# SlopeGenerator.net
KiCad netlist of a schematic drawn in EAGLE
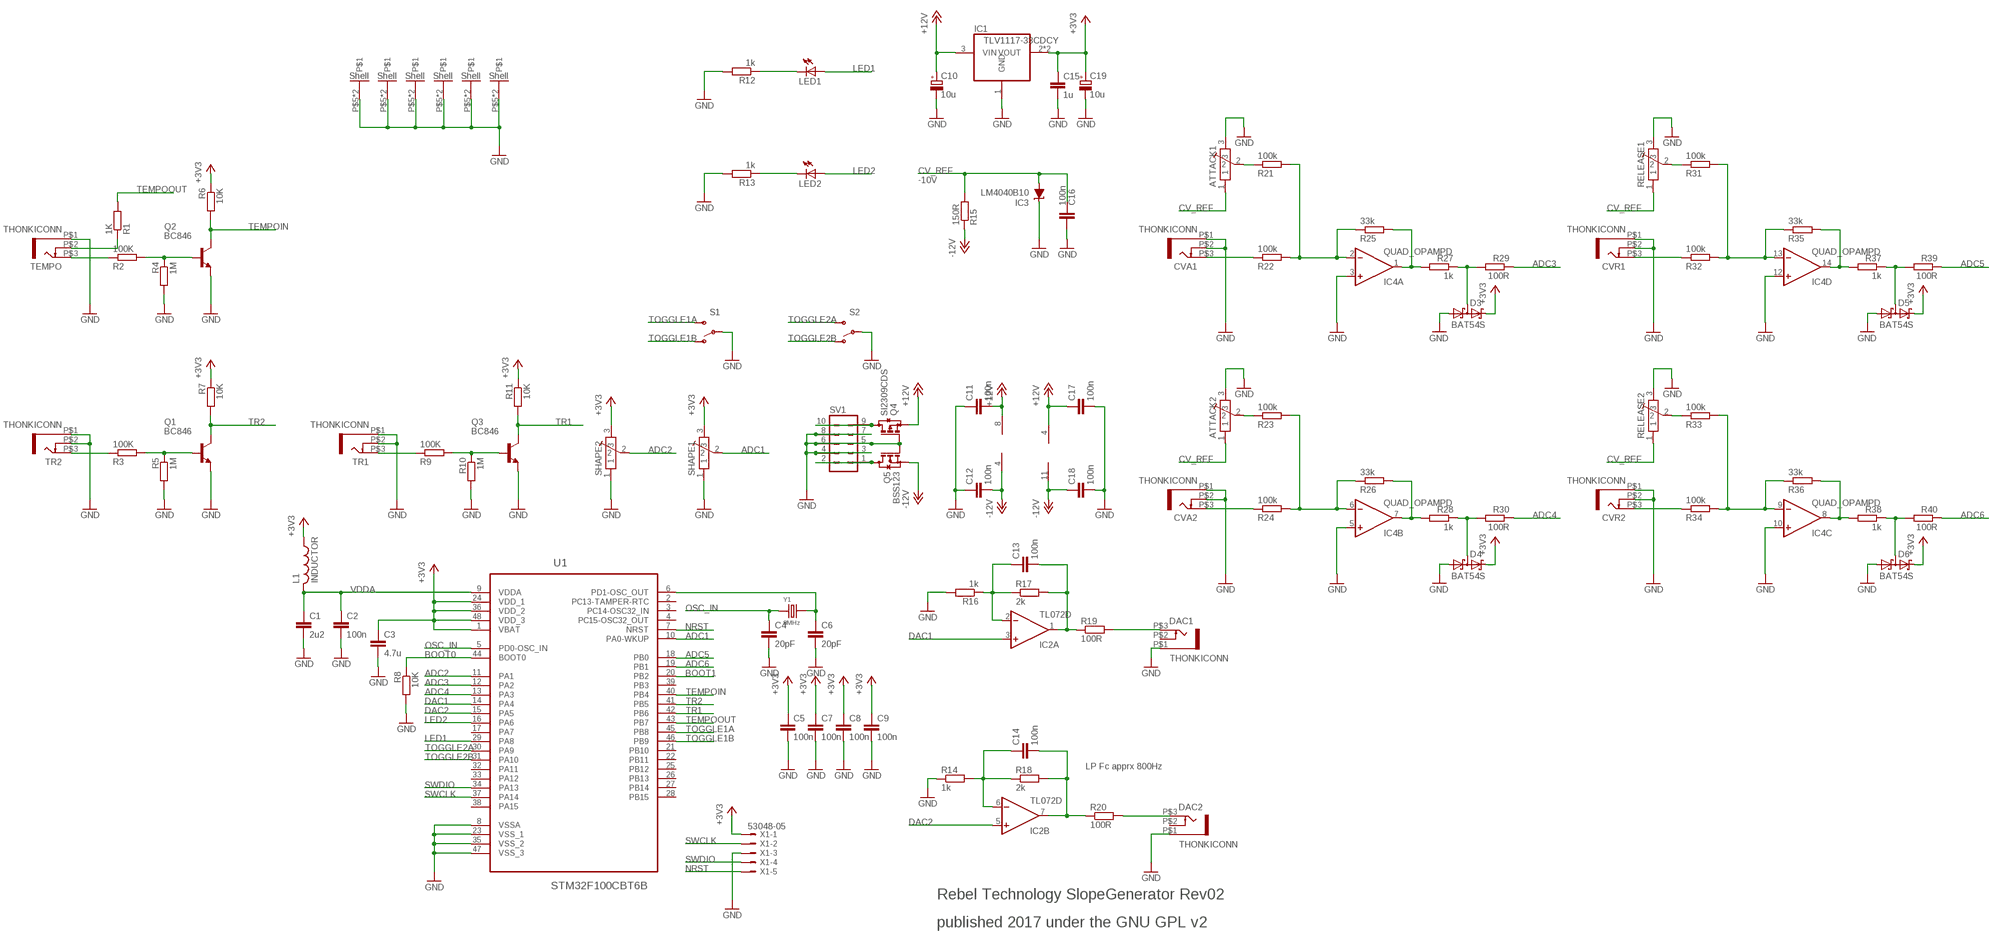
[diagram p0: schematic, sheet 1]

(export (version "E")
  (design (tool "Eeschema 10.0.6"))
  (components
    (comp (ref "ATTACK1")
      (value "POT-ALPS-RK09L1140")
      (footprint "eagle-import:POT-ALPS-RK09L1140")
      (libsource (lib "eagle-import") (part "POT-ALPS-RK09L1140"))
    )
    (comp (ref "ATTACK2")
      (value "POT-ALPS-RK09L1140")
      (footprint "eagle-import:POT-ALPS-RK09L1140")
      (libsource (lib "eagle-import") (part "POT-ALPS-RK09L1140"))
    )
    (comp (ref "C1")
      (value "2u2")
      (footprint "eagle-import:C0603")
      (libsource (lib "eagle-import") (part "C-EUC0603"))
    )
    (comp (ref "C2")
      (value "100n")
      (footprint "eagle-import:C0603")
      (libsource (lib "eagle-import") (part "C-EUC0603"))
    )
    (comp (ref "C3")
      (value "4.7u")
      (footprint "eagle-import:C0603")
      (libsource (lib "eagle-import") (part "C-EUC0603"))
    )
    (comp (ref "C4")
      (value "20pF")
      (footprint "eagle-import:C0603")
      (libsource (lib "eagle-import") (part "C-EUC0603"))
    )
    (comp (ref "C5")
      (value "100n")
      (footprint "eagle-import:C0603")
      (libsource (lib "eagle-import") (part "C-EUC0603"))
    )
    (comp (ref "C6")
      (value "20pF")
      (footprint "eagle-import:C0603")
      (libsource (lib "eagle-import") (part "C-EUC0603"))
    )
    (comp (ref "C7")
      (value "100n")
      (footprint "eagle-import:C0603")
      (libsource (lib "eagle-import") (part "C-EUC0603"))
    )
    (comp (ref "C8")
      (value "100n")
      (footprint "eagle-import:C0603")
      (libsource (lib "eagle-import") (part "C-EUC0603"))
    )
    (comp (ref "C9")
      (value "100n")
      (footprint "eagle-import:C0603")
      (libsource (lib "eagle-import") (part "C-EUC0603"))
    )
    (comp (ref "C10")
      (value "10u")
      (footprint "eagle-import:153CLV-0405")
      (libsource (lib "eagle-import") (part "CPOL-EU153CLV-0405"))
    )
    (comp (ref "C11")
      (value "100n")
      (footprint "eagle-import:C0603")
      (libsource (lib "eagle-import") (part "C-EUC0603"))
    )
    (comp (ref "C12")
      (value "100n")
      (footprint "eagle-import:C0603")
      (libsource (lib "eagle-import") (part "C-EUC0603"))
    )
    (comp (ref "C13")
      (value "100n")
      (footprint "eagle-import:C0603")
      (libsource (lib "eagle-import") (part "C-EUC0603"))
    )
    (comp (ref "C14")
      (value "100n")
      (footprint "eagle-import:C0603")
      (libsource (lib "eagle-import") (part "C-EUC0603"))
    )
    (comp (ref "C15")
      (value "1u")
      (footprint "eagle-import:C0603")
      (libsource (lib "eagle-import") (part "C-EUC0603"))
    )
    (comp (ref "C16")
      (value "100n")
      (footprint "eagle-import:C0603")
      (libsource (lib "eagle-import") (part "C-EUC0603"))
    )
    (comp (ref "C17")
      (value "100n")
      (footprint "eagle-import:C0603")
      (libsource (lib "eagle-import") (part "C-EUC0603"))
    )
    (comp (ref "C18")
      (value "100n")
      (footprint "eagle-import:C0603")
      (libsource (lib "eagle-import") (part "C-EUC0603"))
    )
    (comp (ref "C19")
      (value "10u")
      (footprint "eagle-import:153CLV-0405")
      (libsource (lib "eagle-import") (part "CPOL-EU153CLV-0405"))
    )
    (comp (ref "CVA1")
      (value "THONKICONN")
      (footprint "eagle-import:THONKICONN")
      (libsource (lib "eagle-import") (part "THONKICONN"))
    )
    (comp (ref "CVA2")
      (value "THONKICONN")
      (footprint "eagle-import:THONKICONN")
      (libsource (lib "eagle-import") (part "THONKICONN"))
    )
    (comp (ref "CVR1")
      (value "THONKICONN")
      (footprint "eagle-import:THONKICONN")
      (libsource (lib "eagle-import") (part "THONKICONN"))
    )
    (comp (ref "CVR2")
      (value "THONKICONN")
      (footprint "eagle-import:THONKICONN")
      (libsource (lib "eagle-import") (part "THONKICONN"))
    )
    (comp (ref "D3")
      (value "BAT54S")
      (footprint "eagle-import:SOT23")
      (libsource (lib "eagle-import") (part "BAT54S"))
    )
    (comp (ref "D4")
      (value "BAT54S")
      (footprint "eagle-import:SOT23")
      (libsource (lib "eagle-import") (part "BAT54S"))
    )
    (comp (ref "D5")
      (value "BAT54S")
      (footprint "eagle-import:SOT23")
      (libsource (lib "eagle-import") (part "BAT54S"))
    )
    (comp (ref "D6")
      (value "BAT54S")
      (footprint "eagle-import:SOT23")
      (libsource (lib "eagle-import") (part "BAT54S"))
    )
    (comp (ref "DAC1")
      (value "THONKICONN")
      (footprint "eagle-import:THONKICONN")
      (libsource (lib "eagle-import") (part "THONKICONN"))
    )
    (comp (ref "DAC2")
      (value "THONKICONN")
      (footprint "eagle-import:THONKICONN")
      (libsource (lib "eagle-import") (part "THONKICONN"))
    )
    (comp (ref "IC1")
      (value "TLV1117-33CDCY")
      (footprint "eagle-import:SOT223")
      (fields (field (name "MPN") "REG1117"))
      (libsource (lib "eagle-import") (part "REG1117"))
    )
    (comp (ref "IC2")
      (value "TL072D")
      (footprint "eagle-import:SO08")
      (libsource (lib "eagle-import") (part "TL072D"))
    )
    (comp (ref "IC3")
      (value "LM4040B10")
      (footprint "eagle-import:DBZ_R-PDSO-G3")
      (fields (field (name "MF") "TEXAS INSTRUMENT CONNECTORS") (field (name "MPN") "LM4041C12QDBZT"))
      (libsource (lib "eagle-import") (part "LM4041DBZC12"))
    )
    (comp (ref "IC4")
      (value "QUAD_OPAMPD")
      (footprint "eagle-import:SO14")
      (libsource (lib "eagle-import") (part "QUAD_OPAMPD"))
    )
    (comp (ref "L1")
      (value "INDUCTOR")
      (footprint "eagle-import:0603")
      (libsource (lib "eagle-import") (part "INDUCTOR"))
    )
    (comp (ref "LED1")
      (value "LED3MM")
      (footprint "eagle-import:LED3MM")
      (libsource (lib "eagle-import") (part "LED3MM"))
    )
    (comp (ref "LED2")
      (value "LED3MM")
      (footprint "eagle-import:LED3MM")
      (libsource (lib "eagle-import") (part "LED3MM"))
    )
    (comp (ref "Q1")
      (value "BC846")
      (footprint "eagle-import:SOT23")
      (libsource (lib "eagle-import") (part "BC846"))
    )
    (comp (ref "Q2")
      (value "BC846")
      (footprint "eagle-import:SOT23")
      (libsource (lib "eagle-import") (part "BC846"))
    )
    (comp (ref "Q3")
      (value "BC846")
      (footprint "eagle-import:SOT23")
      (libsource (lib "eagle-import") (part "BC846"))
    )
    (comp (ref "Q4")
      (value "SI2309CDS")
      (footprint "eagle-import:SOT23")
      (libsource (lib "eagle-import") (part "BSS84"))
    )
    (comp (ref "Q5")
      (value "BSS123")
      (footprint "eagle-import:SOT23")
      (libsource (lib "eagle-import") (part "BSS123"))
    )
    (comp (ref "R1")
      (value "1K")
      (footprint "eagle-import:0603")
      (libsource (lib "eagle-import") (part "R-EU_0603"))
    )
    (comp (ref "R2")
      (value "100K")
      (footprint "eagle-import:0603")
      (libsource (lib "eagle-import") (part "R-EU_0603"))
    )
    (comp (ref "R3")
      (value "100K")
      (footprint "eagle-import:0603")
      (libsource (lib "eagle-import") (part "R-EU_0603"))
    )
    (comp (ref "R4")
      (value "1M")
      (footprint "eagle-import:0603")
      (libsource (lib "eagle-import") (part "R-EU_0603"))
    )
    (comp (ref "R5")
      (value "1M")
      (footprint "eagle-import:0603")
      (libsource (lib "eagle-import") (part "R-EU_0603"))
    )
    (comp (ref "R6")
      (value "10K")
      (footprint "eagle-import:0603")
      (libsource (lib "eagle-import") (part "R-EU_0603"))
    )
    (comp (ref "R7")
      (value "10K")
      (footprint "eagle-import:0603")
      (libsource (lib "eagle-import") (part "R-EU_0603"))
    )
    (comp (ref "R8")
      (value "10K")
      (footprint "eagle-import:0603")
      (libsource (lib "eagle-import") (part "R-EU_0603"))
    )
    (comp (ref "R9")
      (value "100K")
      (footprint "eagle-import:0603")
      (libsource (lib "eagle-import") (part "R-EU_0603"))
    )
    (comp (ref "R10")
      (value "1M")
      (footprint "eagle-import:0603")
      (libsource (lib "eagle-import") (part "R-EU_0603"))
    )
    (comp (ref "R11")
      (value "10K")
      (footprint "eagle-import:0603")
      (libsource (lib "eagle-import") (part "R-EU_0603"))
    )
    (comp (ref "R12")
      (value "1k")
      (footprint "eagle-import:0603")
      (libsource (lib "eagle-import") (part "R-EU_0603"))
    )
    (comp (ref "R13")
      (value "1k")
      (footprint "eagle-import:0603")
      (libsource (lib "eagle-import") (part "R-EU_0603"))
    )
    (comp (ref "R14")
      (value "1k")
      (footprint "eagle-import:0603")
      (libsource (lib "eagle-import") (part "R-EU_0603"))
    )
    (comp (ref "R15")
      (value "150R")
      (footprint "eagle-import:0603")
      (libsource (lib "eagle-import") (part "R-EU_0603"))
    )
    (comp (ref "R16")
      (value "1k")
      (footprint "eagle-import:0603")
      (libsource (lib "eagle-import") (part "R-EU_0603"))
    )
    (comp (ref "R17")
      (value "2k")
      (footprint "eagle-import:0603")
      (libsource (lib "eagle-import") (part "R-EU_0603"))
    )
    (comp (ref "R18")
      (value "2k")
      (footprint "eagle-import:0603")
      (libsource (lib "eagle-import") (part "R-EU_0603"))
    )
    (comp (ref "R19")
      (value "100R")
      (footprint "eagle-import:0603")
      (libsource (lib "eagle-import") (part "R-EU_0603"))
    )
    (comp (ref "R20")
      (value "100R")
      (footprint "eagle-import:0603")
      (libsource (lib "eagle-import") (part "R-EU_0603"))
    )
    (comp (ref "R21")
      (value "100k")
      (footprint "eagle-import:0603")
      (libsource (lib "eagle-import") (part "R-EU_0603"))
    )
    (comp (ref "R22")
      (value "100k")
      (footprint "eagle-import:0603")
      (libsource (lib "eagle-import") (part "R-EU_0603"))
    )
    (comp (ref "R23")
      (value "100k")
      (footprint "eagle-import:0603")
      (libsource (lib "eagle-import") (part "R-EU_0603"))
    )
    (comp (ref "R24")
      (value "100k")
      (footprint "eagle-import:0603")
      (libsource (lib "eagle-import") (part "R-EU_0603"))
    )
    (comp (ref "R25")
      (value "33k")
      (footprint "eagle-import:0603")
      (libsource (lib "eagle-import") (part "R-EU_0603"))
    )
    (comp (ref "R26")
      (value "33k")
      (footprint "eagle-import:0603")
      (libsource (lib "eagle-import") (part "R-EU_0603"))
    )
    (comp (ref "R27")
      (value "1k")
      (footprint "eagle-import:0603")
      (libsource (lib "eagle-import") (part "R-EU_0603"))
    )
    (comp (ref "R28")
      (value "1k")
      (footprint "eagle-import:0603")
      (libsource (lib "eagle-import") (part "R-EU_0603"))
    )
    (comp (ref "R29")
      (value "100R")
      (footprint "eagle-import:0603")
      (libsource (lib "eagle-import") (part "R-EU_0603"))
    )
    (comp (ref "R30")
      (value "100R")
      (footprint "eagle-import:0603")
      (libsource (lib "eagle-import") (part "R-EU_0603"))
    )
    (comp (ref "R31")
      (value "100k")
      (footprint "eagle-import:0603")
      (libsource (lib "eagle-import") (part "R-EU_0603"))
    )
    (comp (ref "R32")
      (value "100k")
      (footprint "eagle-import:0603")
      (libsource (lib "eagle-import") (part "R-EU_0603"))
    )
    (comp (ref "R33")
      (value "100k")
      (footprint "eagle-import:0603")
      (libsource (lib "eagle-import") (part "R-EU_0603"))
    )
    (comp (ref "R34")
      (value "100k")
      (footprint "eagle-import:0603")
      (libsource (lib "eagle-import") (part "R-EU_0603"))
    )
    (comp (ref "R35")
      (value "33k")
      (footprint "eagle-import:0603")
      (libsource (lib "eagle-import") (part "R-EU_0603"))
    )
    (comp (ref "R36")
      (value "33k")
      (footprint "eagle-import:0603")
      (libsource (lib "eagle-import") (part "R-EU_0603"))
    )
    (comp (ref "R37")
      (value "1k")
      (footprint "eagle-import:0603")
      (libsource (lib "eagle-import") (part "R-EU_0603"))
    )
    (comp (ref "R38")
      (value "1k")
      (footprint "eagle-import:0603")
      (libsource (lib "eagle-import") (part "R-EU_0603"))
    )
    (comp (ref "R39")
      (value "100R")
      (footprint "eagle-import:0603")
      (libsource (lib "eagle-import") (part "R-EU_0603"))
    )
    (comp (ref "R40")
      (value "100R")
      (footprint "eagle-import:0603")
      (libsource (lib "eagle-import") (part "R-EU_0603"))
    )
    (comp (ref "RELEASE1")
      (value "POT-ALPS-RK09L1140")
      (footprint "eagle-import:POT-ALPS-RK09L1140")
      (libsource (lib "eagle-import") (part "POT-ALPS-RK09L1140"))
    )
    (comp (ref "RELEASE2")
      (value "POT-ALPS-RK09L1140")
      (footprint "eagle-import:POT-ALPS-RK09L1140")
      (libsource (lib "eagle-import") (part "POT-ALPS-RK09L1140"))
    )
    (comp (ref "S1")
      (value "SWITCH-SPST")
      (footprint "eagle-import:SWITCH-SPDT-SALECOM-T8014")
      (libsource (lib "eagle-import") (part "SWITCH-SPST"))
    )
    (comp (ref "S2")
      (value "SWITCH-SPST")
      (footprint "eagle-import:SWITCH-SPDT-SALECOM-T8014")
      (libsource (lib "eagle-import") (part "SWITCH-SPST"))
    )
    (comp (ref "SHAPE1")
      (value "POT-ALPS-RK09L1140")
      (footprint "eagle-import:POT-ALPS-RK09L1140")
      (libsource (lib "eagle-import") (part "POT-ALPS-RK09L1140"))
    )
    (comp (ref "SHAPE2")
      (value "POT-ALPS-RK09L1140")
      (footprint "eagle-import:POT-ALPS-RK09L1140")
      (libsource (lib "eagle-import") (part "POT-ALPS-RK09L1140"))
    )
    (comp (ref "SV1")
      (value "MA05-2")
      (footprint "eagle-import:MA05-2")
      (libsource (lib "eagle-import") (part "MA05-2"))
    )
    (comp (ref "TEMPO")
      (value "THONKICONN")
      (footprint "eagle-import:THONKICONN")
      (libsource (lib "eagle-import") (part "THONKICONN"))
    )
    (comp (ref "TR1")
      (value "THONKICONN")
      (footprint "eagle-import:THONKICONN")
      (libsource (lib "eagle-import") (part "THONKICONN"))
    )
    (comp (ref "TR2")
      (value "THONKICONN")
      (footprint "eagle-import:THONKICONN")
      (libsource (lib "eagle-import") (part "THONKICONN"))
    )
    (comp (ref "U1")
      (value "STM32F100CBT6B")
      (footprint "eagle-import:QFP50P900X900X160-48N")
      (libsource (lib "eagle-import") (part "STM32F100CBT6B"))
    )
    (comp (ref "X1")
      (value "53048-05")
      (footprint "eagle-import:53048-05")
      (fields (field (name "MF") "MOLEX") (field (name "MPN") "53048-0510"))
      (libsource (lib "eagle-import") (part "53?-05048"))
    )
    (comp (ref "Y1")
      (value "8MHz")
      (footprint "eagle-import:X2-SMD-5.0X3.2X1.3MM")
      (fields (field (name "MPN") "5032/2P"))
      (libsource (lib "eagle-import") (part "SMD-CRYSTAL-8MHZ-20PF-20PPM(2P-5.0X3.2MM)"))
    )
  )
  (nets
    (net (code "1") (name "+3V3") (class "Default")
      (node (ref "C15") (pin "1") (pinfunction "1_1") (pintype "passive"))
      (node (ref "C19") (pin "+") (pinfunction "+_+") (pintype "passive"))
      (node (ref "C3") (pin "1") (pinfunction "1_1") (pintype "passive"))
      (node (ref "C5") (pin "1") (pinfunction "1_1") (pintype "passive"))
      (node (ref "C7") (pin "1") (pinfunction "1_1") (pintype "passive"))
      (node (ref "C8") (pin "1") (pinfunction "1_1") (pintype "passive"))
      (node (ref "C9") (pin "1") (pinfunction "1_1") (pintype "passive"))
      (node (ref "D3") (pin "2") (pinfunction "C2_2") (pintype "passive"))
      (node (ref "D4") (pin "2") (pinfunction "C2_2") (pintype "passive"))
      (node (ref "D5") (pin "2") (pinfunction "C2_2") (pintype "passive"))
      (node (ref "D6") (pin "2") (pinfunction "C2_2") (pintype "passive"))
      (node (ref "IC1") (pin "2") (pinfunction "VOUT_2") (pintype "output"))
      (node (ref "IC1") (pin "4") (pinfunction "VOUT_4") (pintype "output"))
      (node (ref "L1") (pin "1") (pinfunction "1_1") (pintype "passive"))
      (node (ref "R11") (pin "1") (pinfunction "1_1") (pintype "passive"))
      (node (ref "R6") (pin "1") (pinfunction "1_1") (pintype "passive"))
      (node (ref "R7") (pin "1") (pinfunction "1_1") (pintype "passive"))
      (node (ref "SHAPE1") (pin "3") (pinfunction "3_3") (pintype "bidirectional"))
      (node (ref "SHAPE2") (pin "3") (pinfunction "3_3") (pintype "bidirectional"))
      (node (ref "U1") (pin "1") (pinfunction "VBAT_1") (pintype "power_in"))
      (node (ref "U1") (pin "24") (pinfunction "VDD_1_24") (pintype "power_in"))
      (node (ref "U1") (pin "36") (pinfunction "VDD_2_36") (pintype "power_in"))
      (node (ref "U1") (pin "48") (pinfunction "VDD_3_48") (pintype "power_in"))
      (node (ref "X1") (pin "1") (pinfunction "S_1") (pintype "passive"))
    )
    (net (code "2") (name "+12V") (class "Default")
      (node (ref "C10") (pin "+") (pinfunction "+_+") (pintype "passive"))
      (node (ref "C11") (pin "2") (pinfunction "2_2") (pintype "passive"))
      (node (ref "C17") (pin "1") (pinfunction "1_1") (pintype "passive"))
      (node (ref "IC1") (pin "3") (pinfunction "VIN_3") (pintype "input"))
      (node (ref "IC2") (pin "8") (pinfunction "V+_8") (pintype "power_in"))
      (node (ref "IC4") (pin "4") (pinfunction "V+_4") (pintype "power_in"))
      (node (ref "Q4") (pin "2") (pinfunction "S_2") (pintype "passive"))
    )
    (net (code "3") (name "-12V") (class "Default")
      (node (ref "C12") (pin "2") (pinfunction "2_2") (pintype "passive"))
      (node (ref "C18") (pin "1") (pinfunction "1_1") (pintype "passive"))
      (node (ref "IC2") (pin "4") (pinfunction "V-_4") (pintype "power_in"))
      (node (ref "IC4") (pin "11") (pinfunction "V-_11") (pintype "power_in"))
      (node (ref "Q5") (pin "2") (pinfunction "S_2") (pintype "passive"))
      (node (ref "R15") (pin "1") (pinfunction "1_1") (pintype "passive"))
    )
    (net (code "4") (name "/ADC1") (class "Default")
      (node (ref "SHAPE1") (pin "2") (pinfunction "2_2") (pintype "bidirectional"))
      (node (ref "U1") (pin "10") (pinfunction "PA0-WKUP_10") (pintype "bidirectional"))
    )
    (net (code "5") (name "/ADC2") (class "Default")
      (node (ref "SHAPE2") (pin "2") (pinfunction "2_2") (pintype "bidirectional"))
      (node (ref "U1") (pin "11") (pinfunction "PA1_11") (pintype "bidirectional"))
    )
    (net (code "6") (name "/ADC3") (class "Default")
      (node (ref "R29") (pin "1") (pinfunction "1_1") (pintype "passive"))
      (node (ref "U1") (pin "12") (pinfunction "PA2_12") (pintype "bidirectional"))
    )
    (net (code "7") (name "/ADC4") (class "Default")
      (node (ref "R30") (pin "1") (pinfunction "1_1") (pintype "passive"))
      (node (ref "U1") (pin "13") (pinfunction "PA3_13") (pintype "bidirectional"))
    )
    (net (code "8") (name "/ADC5") (class "Default")
      (node (ref "R39") (pin "1") (pinfunction "1_1") (pintype "passive"))
      (node (ref "U1") (pin "18") (pinfunction "PB0_18") (pintype "bidirectional"))
    )
    (net (code "9") (name "/ADC6") (class "Default")
      (node (ref "R40") (pin "1") (pinfunction "1_1") (pintype "passive"))
      (node (ref "U1") (pin "19") (pinfunction "PB1_19") (pintype "bidirectional"))
    )
    (net (code "10") (name "/BOOT0") (class "Default")
      (node (ref "R8") (pin "1") (pinfunction "1_1") (pintype "passive"))
      (node (ref "U1") (pin "44") (pinfunction "BOOT0_44") (pintype "input"))
    )
    (net (code "11") (name "/BOOT1") (class "Default")
      (node (ref "U1") (pin "20") (pinfunction "PB2_20") (pintype "bidirectional"))
    )
    (net (code "12") (name "/CV_REF") (class "Default")
      (node (ref "ATTACK1") (pin "1") (pinfunction "1_1") (pintype "bidirectional"))
      (node (ref "ATTACK2") (pin "1") (pinfunction "1_1") (pintype "bidirectional"))
      (node (ref "C16") (pin "1") (pinfunction "1_1") (pintype "passive"))
      (node (ref "IC3") (pin "2") (pinfunction "A_2") (pintype "passive"))
      (node (ref "R15") (pin "2") (pinfunction "2_2") (pintype "passive"))
      (node (ref "RELEASE1") (pin "1") (pinfunction "1_1") (pintype "bidirectional"))
      (node (ref "RELEASE2") (pin "1") (pinfunction "1_1") (pintype "bidirectional"))
    )
    (net (code "13") (name "/DAC1") (class "Default")
      (node (ref "IC2") (pin "3") (pinfunction "+IN_3") (pintype "input"))
      (node (ref "U1") (pin "14") (pinfunction "PA4_14") (pintype "bidirectional"))
    )
    (net (code "14") (name "/DAC2") (class "Default")
      (node (ref "IC2") (pin "5") (pinfunction "+IN_5") (pintype "input"))
      (node (ref "U1") (pin "15") (pinfunction "PA5_15") (pintype "bidirectional"))
    )
    (net (code "15") (name "/LED1") (class "Default")
      (node (ref "LED1") (pin "A") (pinfunction "A_A") (pintype "passive"))
      (node (ref "U1") (pin "29") (pinfunction "PA8_29") (pintype "bidirectional"))
    )
    (net (code "16") (name "/LED2") (class "Default")
      (node (ref "LED2") (pin "A") (pinfunction "A_A") (pintype "passive"))
      (node (ref "U1") (pin "16") (pinfunction "PA6_16") (pintype "bidirectional"))
    )
    (net (code "17") (name "/NRST") (class "Default")
      (node (ref "U1") (pin "7") (pinfunction "NRST_7") (pintype "bidirectional"))
      (node (ref "X1") (pin "5") (pinfunction "S_5") (pintype "passive"))
    )
    (net (code "18") (name "/OSC_IN") (class "Default")
      (node (ref "C4") (pin "1") (pinfunction "1_1") (pintype "passive"))
      (node (ref "U1") (pin "5") (pinfunction "PD0-OSC_IN_5") (pintype "input"))
      (node (ref "Y1") (pin "1") (pinfunction "1_1") (pintype "passive"))
    )
    (net (code "19") (name "/SWCLK") (class "Default")
      (node (ref "U1") (pin "37") (pinfunction "PA14_37") (pintype "bidirectional"))
      (node (ref "X1") (pin "2") (pinfunction "S_2") (pintype "passive"))
    )
    (net (code "20") (name "/SWDIO") (class "Default")
      (node (ref "U1") (pin "34") (pinfunction "PA13_34") (pintype "bidirectional"))
      (node (ref "X1") (pin "4") (pinfunction "S_4") (pintype "passive"))
    )
    (net (code "21") (name "/TEMPOIN") (class "Default")
      (node (ref "Q2") (pin "3") (pinfunction "C_3") (pintype "passive"))
      (node (ref "R6") (pin "2") (pinfunction "2_2") (pintype "passive"))
      (node (ref "U1") (pin "40") (pinfunction "PB4_40") (pintype "bidirectional"))
    )
    (net (code "22") (name "/TEMPOOUT") (class "Default")
      (node (ref "R1") (pin "2") (pinfunction "2_2") (pintype "passive"))
      (node (ref "U1") (pin "43") (pinfunction "PB7_43") (pintype "bidirectional"))
    )
    (net (code "23") (name "/TOGGLE1A") (class "Default")
      (node (ref "S1") (pin "3") (pinfunction "S_3") (pintype "passive"))
      (node (ref "U1") (pin "45") (pinfunction "PB8_45") (pintype "bidirectional"))
    )
    (net (code "24") (name "/TOGGLE1B") (class "Default")
      (node (ref "S1") (pin "1") (pinfunction "O_1") (pintype "passive"))
      (node (ref "U1") (pin "46") (pinfunction "PB9_46") (pintype "bidirectional"))
    )
    (net (code "25") (name "/TOGGLE2A") (class "Default")
      (node (ref "S2") (pin "3") (pinfunction "S_3") (pintype "passive"))
      (node (ref "U1") (pin "30") (pinfunction "PA9_30") (pintype "bidirectional"))
    )
    (net (code "26") (name "/TOGGLE2B") (class "Default")
      (node (ref "S2") (pin "1") (pinfunction "O_1") (pintype "passive"))
      (node (ref "U1") (pin "31") (pinfunction "PA10_31") (pintype "bidirectional"))
    )
    (net (code "27") (name "/TR1") (class "Default")
      (node (ref "Q3") (pin "3") (pinfunction "C_3") (pintype "passive"))
      (node (ref "R11") (pin "2") (pinfunction "2_2") (pintype "passive"))
      (node (ref "U1") (pin "42") (pinfunction "PB6_42") (pintype "bidirectional"))
    )
    (net (code "28") (name "/TR2") (class "Default")
      (node (ref "Q1") (pin "3") (pinfunction "C_3") (pintype "passive"))
      (node (ref "R7") (pin "2") (pinfunction "2_2") (pintype "passive"))
      (node (ref "U1") (pin "41") (pinfunction "PB5_41") (pintype "bidirectional"))
    )
    (net (code "29") (name "/VDDA") (class "Default")
      (node (ref "C1") (pin "1") (pinfunction "1_1") (pintype "passive"))
      (node (ref "C2") (pin "1") (pinfunction "1_1") (pintype "passive"))
      (node (ref "L1") (pin "2") (pinfunction "2_2") (pintype "passive"))
      (node (ref "U1") (pin "9") (pinfunction "VDDA_9") (pintype "power_in"))
    )
    (net (code "30") (name "GND") (class "Default")
      (node (ref "ATTACK1") (pin "3") (pinfunction "3_3") (pintype "bidirectional"))
      (node (ref "ATTACK1") (pin "P$5") (pinfunction "P$1_P$5") (pintype "bidirectional"))
      (node (ref "ATTACK1") (pin "P$6") (pinfunction "P$1_P$6") (pintype "bidirectional"))
      (node (ref "ATTACK2") (pin "3") (pinfunction "3_3") (pintype "bidirectional"))
      (node (ref "ATTACK2") (pin "P$5") (pinfunction "P$1_P$5") (pintype "bidirectional"))
      (node (ref "ATTACK2") (pin "P$6") (pinfunction "P$1_P$6") (pintype "bidirectional"))
      (node (ref "C1") (pin "2") (pinfunction "2_2") (pintype "passive"))
      (node (ref "C10") (pin "-") (pinfunction "-_-") (pintype "passive"))
      (node (ref "C11") (pin "1") (pinfunction "1_1") (pintype "passive"))
      (node (ref "C12") (pin "1") (pinfunction "1_1") (pintype "passive"))
      (node (ref "C15") (pin "2") (pinfunction "2_2") (pintype "passive"))
      (node (ref "C16") (pin "2") (pinfunction "2_2") (pintype "passive"))
      (node (ref "C17") (pin "2") (pinfunction "2_2") (pintype "passive"))
      (node (ref "C18") (pin "2") (pinfunction "2_2") (pintype "passive"))
      (node (ref "C19") (pin "-") (pinfunction "-_-") (pintype "passive"))
      (node (ref "C2") (pin "2") (pinfunction "2_2") (pintype "passive"))
      (node (ref "C3") (pin "2") (pinfunction "2_2") (pintype "passive"))
      (node (ref "C4") (pin "2") (pinfunction "2_2") (pintype "passive"))
      (node (ref "C5") (pin "2") (pinfunction "2_2") (pintype "passive"))
      (node (ref "C6") (pin "2") (pinfunction "2_2") (pintype "passive"))
      (node (ref "C7") (pin "2") (pinfunction "2_2") (pintype "passive"))
      (node (ref "C8") (pin "2") (pinfunction "2_2") (pintype "passive"))
      (node (ref "C9") (pin "2") (pinfunction "2_2") (pintype "passive"))
      (node (ref "CVA1") (pin "P$1") (pinfunction "5_P$1") (pintype "passive"))
      (node (ref "CVA1") (pin "P$2") (pinfunction "4_P$2") (pintype "passive"))
      (node (ref "CVA2") (pin "P$1") (pinfunction "5_P$1") (pintype "passive"))
      (node (ref "CVA2") (pin "P$2") (pinfunction "4_P$2") (pintype "passive"))
      (node (ref "CVR1") (pin "P$1") (pinfunction "5_P$1") (pintype "passive"))
      (node (ref "CVR1") (pin "P$2") (pinfunction "4_P$2") (pintype "passive"))
      (node (ref "CVR2") (pin "P$1") (pinfunction "5_P$1") (pintype "passive"))
      (node (ref "CVR2") (pin "P$2") (pinfunction "4_P$2") (pintype "passive"))
      (node (ref "D3") (pin "1") (pinfunction "A1_1") (pintype "passive"))
      (node (ref "D4") (pin "1") (pinfunction "A1_1") (pintype "passive"))
      (node (ref "D5") (pin "1") (pinfunction "A1_1") (pintype "passive"))
      (node (ref "D6") (pin "1") (pinfunction "A1_1") (pintype "passive"))
      (node (ref "DAC1") (pin "P$1") (pinfunction "5_P$1") (pintype "passive"))
      (node (ref "DAC2") (pin "P$1") (pinfunction "5_P$1") (pintype "passive"))
      (node (ref "IC1") (pin "1") (pinfunction "GND_1") (pintype "power_in"))
      (node (ref "IC3") (pin "1") (pinfunction "C_1") (pintype "passive"))
      (node (ref "IC4") (pin "10") (pinfunction "+IN_10") (pintype "input"))
      (node (ref "IC4") (pin "12") (pinfunction "+IN_12") (pintype "input"))
      (node (ref "IC4") (pin "3") (pinfunction "+IN_3") (pintype "input"))
      (node (ref "IC4") (pin "5") (pinfunction "+IN_5") (pintype "input"))
      (node (ref "Q1") (pin "2") (pinfunction "E_2") (pintype "passive"))
      (node (ref "Q2") (pin "2") (pinfunction "E_2") (pintype "passive"))
      (node (ref "Q3") (pin "2") (pinfunction "E_2") (pintype "passive"))
      (node (ref "Q4") (pin "1") (pinfunction "G_1") (pintype "passive"))
      (node (ref "Q5") (pin "1") (pinfunction "G_1") (pintype "passive"))
      (node (ref "R10") (pin "2") (pinfunction "2_2") (pintype "passive"))
      (node (ref "R12") (pin "2") (pinfunction "2_2") (pintype "passive"))
      (node (ref "R13") (pin "2") (pinfunction "2_2") (pintype "passive"))
      (node (ref "R14") (pin "1") (pinfunction "1_1") (pintype "passive"))
      (node (ref "R16") (pin "2") (pinfunction "2_2") (pintype "passive"))
      (node (ref "R4") (pin "2") (pinfunction "2_2") (pintype "passive"))
      (node (ref "R5") (pin "2") (pinfunction "2_2") (pintype "passive"))
      (node (ref "R8") (pin "2") (pinfunction "2_2") (pintype "passive"))
      (node (ref "RELEASE1") (pin "3") (pinfunction "3_3") (pintype "bidirectional"))
      (node (ref "RELEASE1") (pin "P$5") (pinfunction "P$1_P$5") (pintype "bidirectional"))
      (node (ref "RELEASE1") (pin "P$6") (pinfunction "P$1_P$6") (pintype "bidirectional"))
      (node (ref "RELEASE2") (pin "3") (pinfunction "3_3") (pintype "bidirectional"))
      (node (ref "RELEASE2") (pin "P$5") (pinfunction "P$1_P$5") (pintype "bidirectional"))
      (node (ref "RELEASE2") (pin "P$6") (pinfunction "P$1_P$6") (pintype "bidirectional"))
      (node (ref "S1") (pin "2") (pinfunction "P_2") (pintype "passive"))
      (node (ref "S2") (pin "2") (pinfunction "P_2") (pintype "passive"))
      (node (ref "SHAPE1") (pin "1") (pinfunction "1_1") (pintype "bidirectional"))
      (node (ref "SHAPE1") (pin "P$5") (pinfunction "P$1_P$5") (pintype "bidirectional"))
      (node (ref "SHAPE1") (pin "P$6") (pinfunction "P$1_P$6") (pintype "bidirectional"))
      (node (ref "SHAPE2") (pin "1") (pinfunction "1_1") (pintype "bidirectional"))
      (node (ref "SHAPE2") (pin "P$5") (pinfunction "P$1_P$5") (pintype "bidirectional"))
      (node (ref "SHAPE2") (pin "P$6") (pinfunction "P$1_P$6") (pintype "bidirectional"))
      (node (ref "SV1") (pin "3") (pinfunction "3_3") (pintype "passive"))
      (node (ref "SV1") (pin "4") (pinfunction "4_4") (pintype "passive"))
      (node (ref "SV1") (pin "5") (pinfunction "5_5") (pintype "passive"))
      (node (ref "SV1") (pin "6") (pinfunction "6_6") (pintype "passive"))
      (node (ref "SV1") (pin "7") (pinfunction "7_7") (pintype "passive"))
      (node (ref "SV1") (pin "8") (pinfunction "8_8") (pintype "passive"))
      (node (ref "TEMPO") (pin "P$1") (pinfunction "5_P$1") (pintype "passive"))
      (node (ref "TR1") (pin "P$1") (pinfunction "5_P$1") (pintype "passive"))
      (node (ref "TR1") (pin "P$2") (pinfunction "4_P$2") (pintype "passive"))
      (node (ref "TR2") (pin "P$1") (pinfunction "5_P$1") (pintype "passive"))
      (node (ref "TR2") (pin "P$2") (pinfunction "4_P$2") (pintype "passive"))
      (node (ref "U1") (pin "23") (pinfunction "VSS_1_23") (pintype "power_in"))
      (node (ref "U1") (pin "35") (pinfunction "VSS_2_35") (pintype "power_in"))
      (node (ref "U1") (pin "47") (pinfunction "VSS_3_47") (pintype "power_in"))
      (node (ref "U1") (pin "8") (pinfunction "VSSA_8") (pintype "power_in"))
      (node (ref "X1") (pin "3") (pinfunction "S_3") (pintype "passive"))
    )
    (net (code "31") (name "Net-(ATTACK1-Pad2)") (class "Default")
      (node (ref "ATTACK1") (pin "2") (pinfunction "2_2") (pintype "bidirectional"))
      (node (ref "R21") (pin "1") (pinfunction "1_1") (pintype "passive"))
    )
    (net (code "32") (name "Net-(ATTACK2-Pad2)") (class "Default")
      (node (ref "ATTACK2") (pin "2") (pinfunction "2_2") (pintype "bidirectional"))
      (node (ref "R23") (pin "1") (pinfunction "1_1") (pintype "passive"))
    )
    (net (code "33") (name "Net-(CVA1-3)") (class "Default")
      (node (ref "CVA1") (pin "P$3") (pinfunction "3_P$3") (pintype "passive"))
      (node (ref "R22") (pin "1") (pinfunction "1_1") (pintype "passive"))
    )
    (net (code "34") (name "Net-(CVA2-3)") (class "Default")
      (node (ref "CVA2") (pin "P$3") (pinfunction "3_P$3") (pintype "passive"))
      (node (ref "R24") (pin "1") (pinfunction "1_1") (pintype "passive"))
    )
    (net (code "35") (name "Net-(CVR1-3)") (class "Default")
      (node (ref "CVR1") (pin "P$3") (pinfunction "3_P$3") (pintype "passive"))
      (node (ref "R32") (pin "1") (pinfunction "1_1") (pintype "passive"))
    )
    (net (code "36") (name "Net-(CVR2-3)") (class "Default")
      (node (ref "CVR2") (pin "P$3") (pinfunction "3_P$3") (pintype "passive"))
      (node (ref "R34") (pin "1") (pinfunction "1_1") (pintype "passive"))
    )
    (net (code "37") (name "Net-(D3-C1A2)") (class "Default")
      (node (ref "D3") (pin "3") (pinfunction "C1A2_3") (pintype "passive"))
      (node (ref "R27") (pin "1") (pinfunction "1_1") (pintype "passive"))
      (node (ref "R29") (pin "2") (pinfunction "2_2") (pintype "passive"))
    )
    (net (code "38") (name "Net-(D4-C1A2)") (class "Default")
      (node (ref "D4") (pin "3") (pinfunction "C1A2_3") (pintype "passive"))
      (node (ref "R28") (pin "1") (pinfunction "1_1") (pintype "passive"))
      (node (ref "R30") (pin "2") (pinfunction "2_2") (pintype "passive"))
    )
    (net (code "39") (name "Net-(D5-C1A2)") (class "Default")
      (node (ref "D5") (pin "3") (pinfunction "C1A2_3") (pintype "passive"))
      (node (ref "R37") (pin "1") (pinfunction "1_1") (pintype "passive"))
      (node (ref "R39") (pin "2") (pinfunction "2_2") (pintype "passive"))
    )
    (net (code "40") (name "Net-(D6-C1A2)") (class "Default")
      (node (ref "D6") (pin "3") (pinfunction "C1A2_3") (pintype "passive"))
      (node (ref "R38") (pin "1") (pinfunction "1_1") (pintype "passive"))
      (node (ref "R40") (pin "2") (pinfunction "2_2") (pintype "passive"))
    )
    (net (code "41") (name "Net-(DAC1-3)") (class "Default")
      (node (ref "DAC1") (pin "P$3") (pinfunction "3_P$3") (pintype "passive"))
      (node (ref "R19") (pin "2") (pinfunction "2_2") (pintype "passive"))
    )
    (net (code "42") (name "Net-(DAC2-3)") (class "Default")
      (node (ref "DAC2") (pin "P$3") (pinfunction "3_P$3") (pintype "passive"))
      (node (ref "R20") (pin "2") (pinfunction "2_2") (pintype "passive"))
    )
    (net (code "43") (name "Net-(IC2A--IN)") (class "Default")
      (node (ref "C13") (pin "1") (pinfunction "1_1") (pintype "passive"))
      (node (ref "IC2") (pin "2") (pinfunction "-IN_2") (pintype "input"))
      (node (ref "R16") (pin "1") (pinfunction "1_1") (pintype "passive"))
      (node (ref "R17") (pin "1") (pinfunction "1_1") (pintype "passive"))
    )
    (net (code "44") (name "Net-(IC2A-OUT)") (class "Default")
      (node (ref "C13") (pin "2") (pinfunction "2_2") (pintype "passive"))
      (node (ref "IC2") (pin "1") (pinfunction "OUT_1") (pintype "output"))
      (node (ref "R17") (pin "2") (pinfunction "2_2") (pintype "passive"))
      (node (ref "R19") (pin "1") (pinfunction "1_1") (pintype "passive"))
    )
    (net (code "45") (name "Net-(IC2B--IN)") (class "Default")
      (node (ref "C14") (pin "1") (pinfunction "1_1") (pintype "passive"))
      (node (ref "IC2") (pin "6") (pinfunction "-IN_6") (pintype "input"))
      (node (ref "R14") (pin "2") (pinfunction "2_2") (pintype "passive"))
      (node (ref "R18") (pin "1") (pinfunction "1_1") (pintype "passive"))
    )
    (net (code "46") (name "Net-(IC2B-OUT)") (class "Default")
      (node (ref "C14") (pin "2") (pinfunction "2_2") (pintype "passive"))
      (node (ref "IC2") (pin "7") (pinfunction "OUT_7") (pintype "output"))
      (node (ref "R18") (pin "2") (pinfunction "2_2") (pintype "passive"))
      (node (ref "R20") (pin "1") (pinfunction "1_1") (pintype "passive"))
    )
    (net (code "47") (name "Net-(IC4A--IN)") (class "Default")
      (node (ref "IC4") (pin "2") (pinfunction "-IN_2") (pintype "input"))
      (node (ref "R21") (pin "2") (pinfunction "2_2") (pintype "passive"))
      (node (ref "R22") (pin "2") (pinfunction "2_2") (pintype "passive"))
      (node (ref "R25") (pin "1") (pinfunction "1_1") (pintype "passive"))
    )
    (net (code "48") (name "Net-(IC4A-OUT)") (class "Default")
      (node (ref "IC4") (pin "1") (pinfunction "OUT_1") (pintype "output"))
      (node (ref "R25") (pin "2") (pinfunction "2_2") (pintype "passive"))
      (node (ref "R27") (pin "2") (pinfunction "2_2") (pintype "passive"))
    )
    (net (code "49") (name "Net-(IC4B--IN)") (class "Default")
      (node (ref "IC4") (pin "6") (pinfunction "-IN_6") (pintype "input"))
      (node (ref "R23") (pin "2") (pinfunction "2_2") (pintype "passive"))
      (node (ref "R24") (pin "2") (pinfunction "2_2") (pintype "passive"))
      (node (ref "R26") (pin "1") (pinfunction "1_1") (pintype "passive"))
    )
    (net (code "50") (name "Net-(IC4B-OUT)") (class "Default")
      (node (ref "IC4") (pin "7") (pinfunction "OUT_7") (pintype "output"))
      (node (ref "R26") (pin "2") (pinfunction "2_2") (pintype "passive"))
      (node (ref "R28") (pin "2") (pinfunction "2_2") (pintype "passive"))
    )
    (net (code "51") (name "Net-(IC4C--IN)") (class "Default")
      (node (ref "IC4") (pin "9") (pinfunction "-IN_9") (pintype "input"))
      (node (ref "R33") (pin "2") (pinfunction "2_2") (pintype "passive"))
      (node (ref "R34") (pin "2") (pinfunction "2_2") (pintype "passive"))
      (node (ref "R36") (pin "1") (pinfunction "1_1") (pintype "passive"))
    )
    (net (code "52") (name "Net-(IC4C-OUT)") (class "Default")
      (node (ref "IC4") (pin "8") (pinfunction "OUT_8") (pintype "output"))
      (node (ref "R36") (pin "2") (pinfunction "2_2") (pintype "passive"))
      (node (ref "R38") (pin "2") (pinfunction "2_2") (pintype "passive"))
    )
    (net (code "53") (name "Net-(IC4D--IN)") (class "Default")
      (node (ref "IC4") (pin "13") (pinfunction "-IN_13") (pintype "input"))
      (node (ref "R31") (pin "2") (pinfunction "2_2") (pintype "passive"))
      (node (ref "R32") (pin "2") (pinfunction "2_2") (pintype "passive"))
      (node (ref "R35") (pin "1") (pinfunction "1_1") (pintype "passive"))
    )
    (net (code "54") (name "Net-(IC4D-OUT)") (class "Default")
      (node (ref "IC4") (pin "14") (pinfunction "OUT_14") (pintype "output"))
      (node (ref "R35") (pin "2") (pinfunction "2_2") (pintype "passive"))
      (node (ref "R37") (pin "2") (pinfunction "2_2") (pintype "passive"))
    )
    (net (code "55") (name "Net-(LED1-C)") (class "Default")
      (node (ref "LED1") (pin "K") (pinfunction "C_K") (pintype "passive"))
      (node (ref "R12") (pin "1") (pinfunction "1_1") (pintype "passive"))
    )
    (net (code "56") (name "Net-(LED2-C)") (class "Default")
      (node (ref "LED2") (pin "K") (pinfunction "C_K") (pintype "passive"))
      (node (ref "R13") (pin "1") (pinfunction "1_1") (pintype "passive"))
    )
    (net (code "57") (name "Net-(Q1-B)") (class "Default")
      (node (ref "Q1") (pin "1") (pinfunction "B_1") (pintype "passive"))
      (node (ref "R3") (pin "2") (pinfunction "2_2") (pintype "passive"))
      (node (ref "R5") (pin "1") (pinfunction "1_1") (pintype "passive"))
    )
    (net (code "58") (name "Net-(Q2-B)") (class "Default")
      (node (ref "Q2") (pin "1") (pinfunction "B_1") (pintype "passive"))
      (node (ref "R2") (pin "2") (pinfunction "2_2") (pintype "passive"))
      (node (ref "R4") (pin "1") (pinfunction "1_1") (pintype "passive"))
    )
    (net (code "59") (name "Net-(Q3-B)") (class "Default")
      (node (ref "Q3") (pin "1") (pinfunction "B_1") (pintype "passive"))
      (node (ref "R10") (pin "1") (pinfunction "1_1") (pintype "passive"))
      (node (ref "R9") (pin "2") (pinfunction "2_2") (pintype "passive"))
    )
    (net (code "60") (name "Net-(Q4-D)") (class "Default")
      (node (ref "Q4") (pin "3") (pinfunction "D_3") (pintype "passive"))
      (node (ref "SV1") (pin "10") (pinfunction "10_10") (pintype "passive"))
      (node (ref "SV1") (pin "9") (pinfunction "9_9") (pintype "passive"))
    )
    (net (code "61") (name "Net-(Q5-D)") (class "Default")
      (node (ref "Q5") (pin "3") (pinfunction "D_3") (pintype "passive"))
      (node (ref "SV1") (pin "1") (pinfunction "1_1") (pintype "passive"))
      (node (ref "SV1") (pin "2") (pinfunction "2_2") (pintype "passive"))
    )
    (net (code "62") (name "Net-(R31-Pad1)") (class "Default")
      (node (ref "R31") (pin "1") (pinfunction "1_1") (pintype "passive"))
      (node (ref "RELEASE1") (pin "2") (pinfunction "2_2") (pintype "bidirectional"))
    )
    (net (code "63") (name "Net-(R33-Pad1)") (class "Default")
      (node (ref "R33") (pin "1") (pinfunction "1_1") (pintype "passive"))
      (node (ref "RELEASE2") (pin "2") (pinfunction "2_2") (pintype "bidirectional"))
    )
    (net (code "64") (name "Net-(TEMPO-3)") (class "Default")
      (node (ref "R2") (pin "1") (pinfunction "1_1") (pintype "passive"))
      (node (ref "TEMPO") (pin "P$3") (pinfunction "3_P$3") (pintype "passive"))
    )
    (net (code "65") (name "Net-(TEMPO-4)") (class "Default")
      (node (ref "R1") (pin "1") (pinfunction "1_1") (pintype "passive"))
      (node (ref "TEMPO") (pin "P$2") (pinfunction "4_P$2") (pintype "passive"))
    )
    (net (code "66") (name "Net-(TR1-3)") (class "Default")
      (node (ref "R9") (pin "1") (pinfunction "1_1") (pintype "passive"))
      (node (ref "TR1") (pin "P$3") (pinfunction "3_P$3") (pintype "passive"))
    )
    (net (code "67") (name "Net-(TR2-3)") (class "Default")
      (node (ref "R3") (pin "1") (pinfunction "1_1") (pintype "passive"))
      (node (ref "TR2") (pin "P$3") (pinfunction "3_P$3") (pintype "passive"))
    )
    (net (code "68") (name "Net-(U1-PD1-OSC_OUT)") (class "Default")
      (node (ref "C6") (pin "1") (pinfunction "1_1") (pintype "passive"))
      (node (ref "U1") (pin "6") (pinfunction "PD1-OSC_OUT_6") (pintype "output"))
      (node (ref "Y1") (pin "2") (pinfunction "2_2") (pintype "passive"))
    )
    (net (code "69") (name "unconnected-(DAC1-4-PadP$2)") (class "Default")
      (node (ref "DAC1") (pin "P$2") (pinfunction "4_P$2") (pintype "passive"))
    )
    (net (code "70") (name "unconnected-(DAC2-4-PadP$2)") (class "Default")
      (node (ref "DAC2") (pin "P$2") (pinfunction "4_P$2") (pintype "passive"))
    )
    (net (code "71") (name "unconnected-(U1-PA7-Pad17)") (class "Default")
      (node (ref "U1") (pin "17") (pinfunction "PA7_17") (pintype "bidirectional"))
    )
    (net (code "72") (name "unconnected-(U1-PA11-Pad32)") (class "Default")
      (node (ref "U1") (pin "32") (pinfunction "PA11_32") (pintype "bidirectional"))
    )
    (net (code "73") (name "unconnected-(U1-PA12-Pad33)") (class "Default")
      (node (ref "U1") (pin "33") (pinfunction "PA12_33") (pintype "bidirectional"))
    )
    (net (code "74") (name "unconnected-(U1-PA15-Pad38)") (class "Default")
      (node (ref "U1") (pin "38") (pinfunction "PA15_38") (pintype "bidirectional"))
    )
    (net (code "75") (name "unconnected-(U1-PB3-Pad39)") (class "Default")
      (node (ref "U1") (pin "39") (pinfunction "PB3_39") (pintype "bidirectional"))
    )
    (net (code "76") (name "unconnected-(U1-PB10-Pad21)") (class "Default")
      (node (ref "U1") (pin "21") (pinfunction "PB10_21") (pintype "bidirectional"))
    )
    (net (code "77") (name "unconnected-(U1-PB11-Pad22)") (class "Default")
      (node (ref "U1") (pin "22") (pinfunction "PB11_22") (pintype "bidirectional"))
    )
    (net (code "78") (name "unconnected-(U1-PB12-Pad25)") (class "Default")
      (node (ref "U1") (pin "25") (pinfunction "PB12_25") (pintype "bidirectional"))
    )
    (net (code "79") (name "unconnected-(U1-PB13-Pad26)") (class "Default")
      (node (ref "U1") (pin "26") (pinfunction "PB13_26") (pintype "bidirectional"))
    )
    (net (code "80") (name "unconnected-(U1-PB14-Pad27)") (class "Default")
      (node (ref "U1") (pin "27") (pinfunction "PB14_27") (pintype "bidirectional"))
    )
    (net (code "81") (name "unconnected-(U1-PB15-Pad28)") (class "Default")
      (node (ref "U1") (pin "28") (pinfunction "PB15_28") (pintype "bidirectional"))
    )
    (net (code "82") (name "unconnected-(U1-PC13-TAMPER-RTC-Pad2)") (class "Default")
      (node (ref "U1") (pin "2") (pinfunction "PC13-TAMPER-RTC_2") (pintype "bidirectional"))
    )
    (net (code "83") (name "unconnected-(U1-PC14-OSC32_IN-Pad3)") (class "Default")
      (node (ref "U1") (pin "3") (pinfunction "PC14-OSC32_IN_3") (pintype "bidirectional"))
    )
    (net (code "84") (name "unconnected-(U1-PC15-OSC32_OUT-Pad4)") (class "Default")
      (node (ref "U1") (pin "4") (pinfunction "PC15-OSC32_OUT_4") (pintype "bidirectional"))
    )
  )
)
